# RHD2132_headstage1.net
KiCad netlist of a schematic drawn in EAGLE
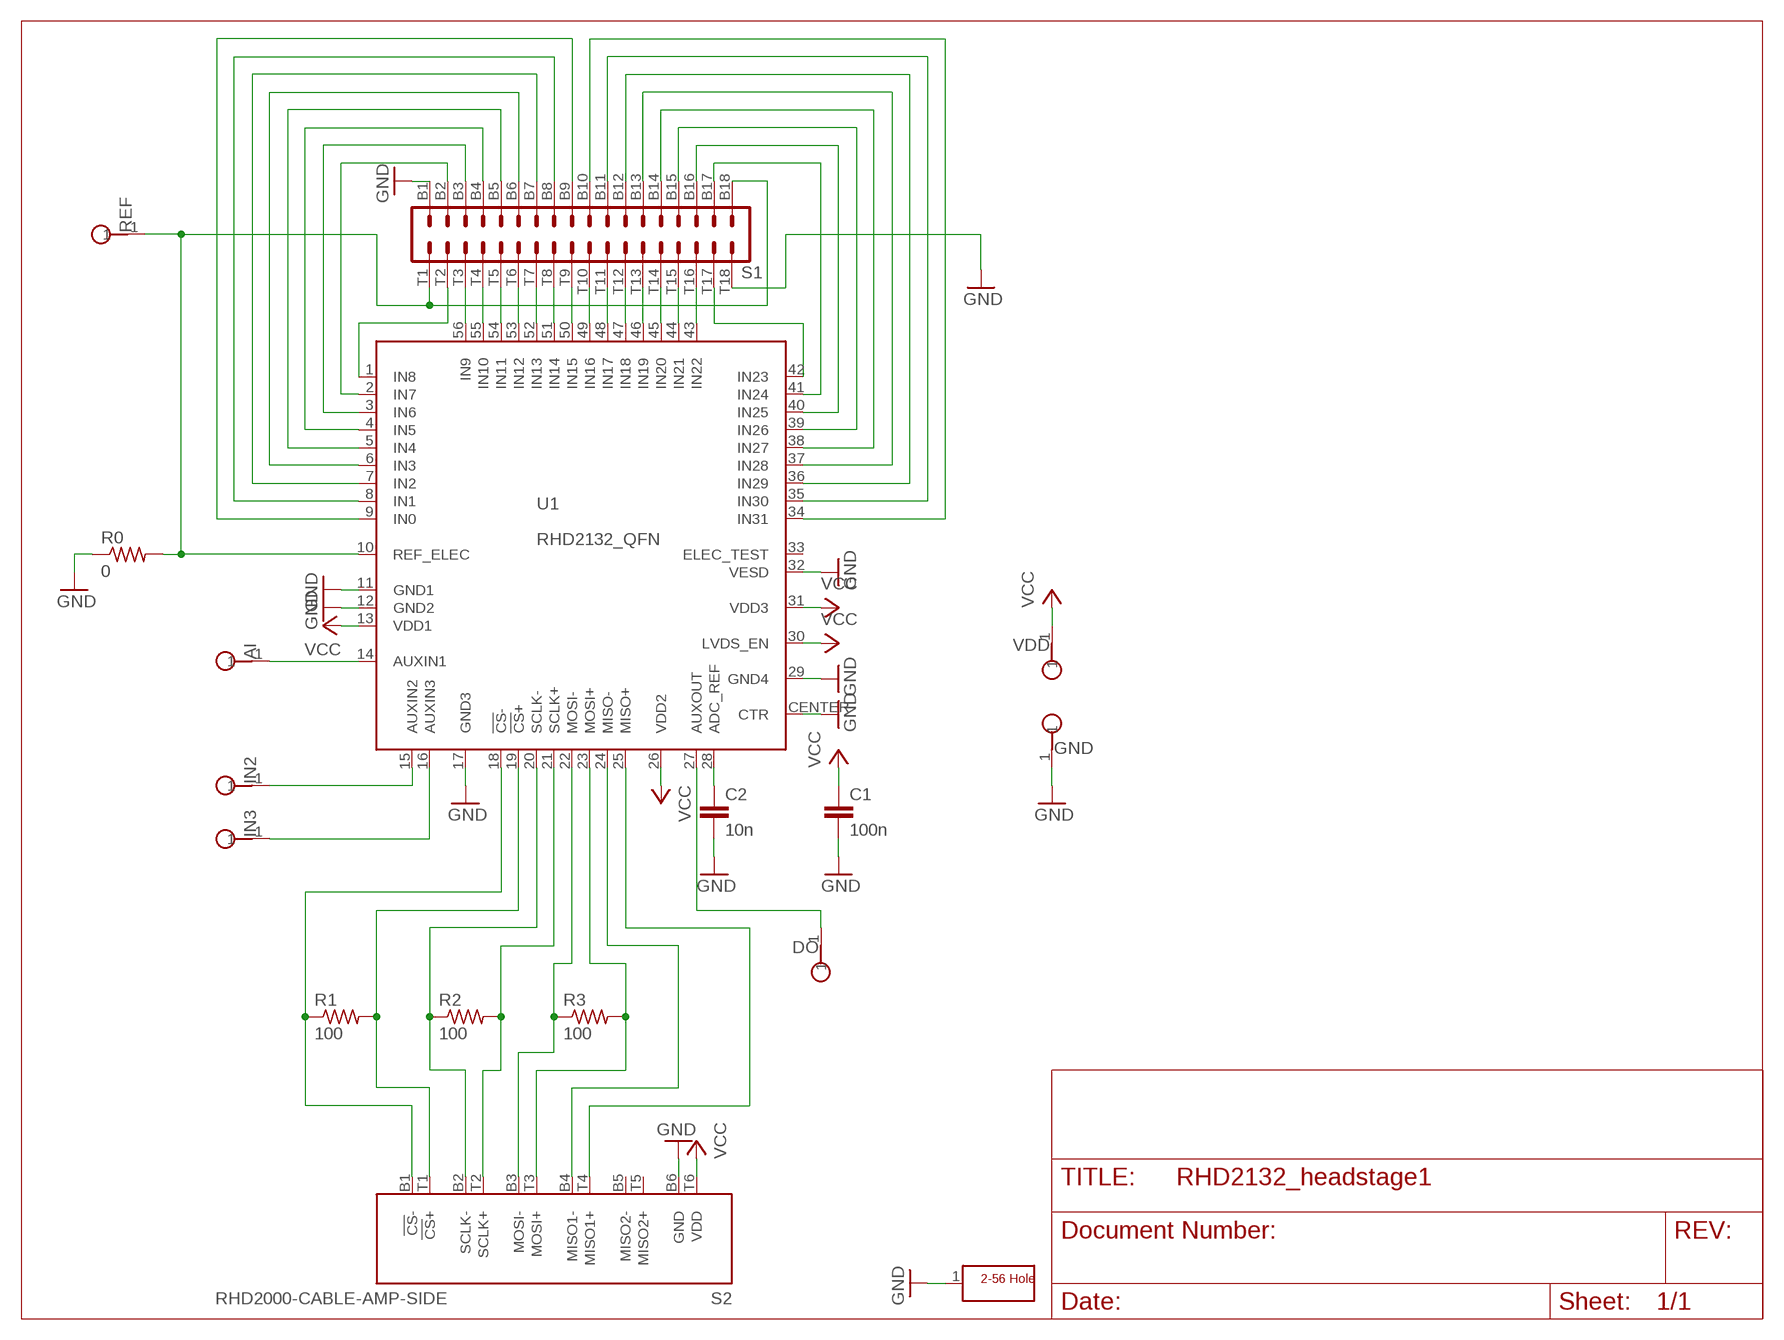
[diagram p0: schematic, sheet 1]

(export (version "E")
  (design (tool "Eeschema 10.0.6"))
  (components
    (comp (ref "AI")
      (value "TESTPOINT_SMALL")
      (footprint "eagle-import:TESTPOINT_SMALL")
      (libsource (lib "eagle-import") (part "TESTPOINT_SMALL"))
    )
    (comp (ref "C1")
      (value "100n")
      (footprint "eagle-import:0402")
      (libsource (lib "eagle-import") (part "C_0402"))
    )
    (comp (ref "C2")
      (value "10n")
      (footprint "eagle-import:0402")
      (libsource (lib "eagle-import") (part "C_0402"))
    )
    (comp (ref "DO")
      (value "TESTPOINT_SMALL")
      (footprint "eagle-import:TESTPOINT_SMALL")
      (libsource (lib "eagle-import") (part "TESTPOINT_SMALL"))
    )
    (comp (ref "GND")
      (value "TESTPOINT_SMALL")
      (footprint "eagle-import:TESTPOINT_SMALL")
      (libsource (lib "eagle-import") (part "TESTPOINT_SMALL"))
    )
    (comp (ref "H1")
      (value "SCREW_HOLE_2-56")
      (footprint "eagle-import:SCREW_HOLE_2-56")
      (libsource (lib "eagle-import") (part "SCREW_HOLE_2-56"))
    )
    (comp (ref "IN2")
      (value "TESTPOINT_SMALL")
      (footprint "eagle-import:TESTPOINT_SMALL")
      (libsource (lib "eagle-import") (part "TESTPOINT_SMALL"))
    )
    (comp (ref "IN3")
      (value "TESTPOINT_SMALL")
      (footprint "eagle-import:TESTPOINT_SMALL")
      (libsource (lib "eagle-import") (part "TESTPOINT_SMALL"))
    )
    (comp (ref "R0")
      (value "0")
      (footprint "eagle-import:0402")
      (libsource (lib "eagle-import") (part "R_0402"))
    )
    (comp (ref "R1")
      (value "100")
      (footprint "eagle-import:0402")
      (libsource (lib "eagle-import") (part "R_0402"))
    )
    (comp (ref "R2")
      (value "100")
      (footprint "eagle-import:0402")
      (libsource (lib "eagle-import") (part "R_0402"))
    )
    (comp (ref "R3")
      (value "100")
      (footprint "eagle-import:0402")
      (libsource (lib "eagle-import") (part "R_0402"))
    )
    (comp (ref "REF")
      (value "TESTPOINT_SMALL")
      (footprint "eagle-import:TESTPOINT_SMALL")
      (libsource (lib "eagle-import") (part "TESTPOINT_SMALL"))
    )
    (comp (ref "S1")
      (value "OMNETICS_A79025")
      (footprint "eagle-import:OMNETICS_A79025")
      (libsource (lib "eagle-import") (part "OMNETICS_A79025"))
    )
    (comp (ref "S2")
      (value "RHD2000-CABLE-AMP-SIDE")
      (footprint "eagle-import:OMNETICS_PZN-12-AA")
      (libsource (lib "eagle-import") (part "RHD2000-CABLE-AMP-SIDE"))
    )
    (comp (ref "U1")
      (value "RHD2132_QFN")
      (footprint "eagle-import:QFN56_8_X_8_LARGE")
      (libsource (lib "eagle-import") (part "RHD2132_QFN"))
    )
    (comp (ref "VDD")
      (value "TESTPOINT_SMALL")
      (footprint "eagle-import:TESTPOINT_SMALL")
      (libsource (lib "eagle-import") (part "TESTPOINT_SMALL"))
    )
  )
  (nets
    (net (code "1") (name "GND") (class "Default")
      (node (ref "C1") (pin "2") (pinfunction "2_2") (pintype "passive"))
      (node (ref "C2") (pin "2") (pinfunction "2_2") (pintype "passive"))
      (node (ref "GND") (pin "1") (pinfunction "1_1") (pintype "passive"))
      (node (ref "H1") (pin "1") (pinfunction "1_1") (pintype "passive"))
      (node (ref "R0") (pin "1") (pinfunction "1_1") (pintype "passive"))
      (node (ref "S1") (pin "B1") (pinfunction "B1_B1") (pintype "passive"))
      (node (ref "S1") (pin "T18") (pinfunction "T18_T18") (pintype "passive"))
      (node (ref "S2") (pin "B6") (pinfunction "GND_B6") (pintype "power_in"))
      (node (ref "U1") (pin "11") (pinfunction "GND1_11") (pintype "power_in"))
      (node (ref "U1") (pin "12") (pinfunction "GND2_12") (pintype "power_in"))
      (node (ref "U1") (pin "17") (pinfunction "GND3_17") (pintype "power_in"))
      (node (ref "U1") (pin "29") (pinfunction "GND4_29") (pintype "power_in"))
      (node (ref "U1") (pin "32") (pinfunction "VESD_32") (pintype "power_in"))
      (node (ref "U1") (pin "CENTER") (pinfunction "CTR_CENTER") (pintype "power_in"))
    )
    (net (code "2") (name "Net-(S2-MISO1+)") (class "Default")
      (node (ref "S2") (pin "T4") (pinfunction "MISO1+_T4") (pintype "bidirectional"))
      (node (ref "U1") (pin "25") (pinfunction "MISO+_25") (pintype "output"))
    )
    (net (code "3") (name "Net-(S2-MISO1-)") (class "Default")
      (node (ref "S2") (pin "B4") (pinfunction "MISO1-_B4") (pintype "bidirectional"))
      (node (ref "U1") (pin "24") (pinfunction "MISO-_24") (pintype "output"))
    )
    (net (code "4") (name "Net-(S2-MOSI+)") (class "Default")
      (node (ref "R3") (pin "2") (pinfunction "2_2") (pintype "passive"))
      (node (ref "S2") (pin "T3") (pinfunction "MOSI+_T3") (pintype "bidirectional"))
      (node (ref "U1") (pin "23") (pinfunction "MOSI+_23") (pintype "input"))
    )
    (net (code "5") (name "Net-(S2-MOSI-)") (class "Default")
      (node (ref "R3") (pin "1") (pinfunction "1_1") (pintype "passive"))
      (node (ref "S2") (pin "B3") (pinfunction "MOSI-_B3") (pintype "bidirectional"))
      (node (ref "U1") (pin "22") (pinfunction "MOSI-_22") (pintype "input"))
    )
    (net (code "6") (name "Net-(S2-SCLK+)") (class "Default")
      (node (ref "R2") (pin "2") (pinfunction "2_2") (pintype "passive"))
      (node (ref "S2") (pin "T2") (pinfunction "SCLK+_T2") (pintype "bidirectional"))
      (node (ref "U1") (pin "21") (pinfunction "SCLK+_21") (pintype "input"))
    )
    (net (code "7") (name "Net-(S2-SCLK-)") (class "Default")
      (node (ref "R2") (pin "1") (pinfunction "1_1") (pintype "passive"))
      (node (ref "S2") (pin "B2") (pinfunction "SCLK-_B2") (pintype "bidirectional"))
      (node (ref "U1") (pin "20") (pinfunction "SCLK-_20") (pintype "input"))
    )
    (net (code "8") (name "Net-(S2-~{CS}+)") (class "Default")
      (node (ref "R1") (pin "2") (pinfunction "2_2") (pintype "passive"))
      (node (ref "S2") (pin "T1") (pinfunction "~{CS}+_T1") (pintype "bidirectional"))
      (node (ref "U1") (pin "19") (pinfunction "~{CS}+_19") (pintype "input"))
    )
    (net (code "9") (name "Net-(S2-~{CS}-)") (class "Default")
      (node (ref "R1") (pin "1") (pinfunction "1_1") (pintype "passive"))
      (node (ref "S2") (pin "B1") (pinfunction "~{CS}-_B1") (pintype "bidirectional"))
      (node (ref "U1") (pin "18") (pinfunction "~{CS}-_18") (pintype "input"))
    )
    (net (code "10") (name "Net-(U1-ADC_REF)") (class "Default")
      (node (ref "C2") (pin "1") (pinfunction "1_1") (pintype "passive"))
      (node (ref "U1") (pin "28") (pinfunction "ADC_REF_28") (pintype "passive"))
    )
    (net (code "11") (name "Net-(U1-AUXIN1)") (class "Default")
      (node (ref "AI") (pin "1") (pinfunction "1_1") (pintype "passive"))
      (node (ref "U1") (pin "14") (pinfunction "AUXIN1_14") (pintype "input"))
    )
    (net (code "12") (name "Net-(U1-AUXIN2)") (class "Default")
      (node (ref "IN2") (pin "1") (pinfunction "1_1") (pintype "passive"))
      (node (ref "U1") (pin "15") (pinfunction "AUXIN2_15") (pintype "input"))
    )
    (net (code "13") (name "Net-(U1-AUXIN3)") (class "Default")
      (node (ref "IN3") (pin "1") (pinfunction "1_1") (pintype "passive"))
      (node (ref "U1") (pin "16") (pinfunction "AUXIN3_16") (pintype "input"))
    )
    (net (code "14") (name "Net-(U1-AUXOUT)") (class "Default")
      (node (ref "DO") (pin "1") (pinfunction "1_1") (pintype "passive"))
      (node (ref "U1") (pin "27") (pinfunction "AUXOUT_27") (pintype "tri_state"))
    )
    (net (code "15") (name "Net-(U1-IN0)") (class "Default")
      (node (ref "S1") (pin "B9") (pinfunction "B9_B9") (pintype "passive"))
      (node (ref "U1") (pin "9") (pinfunction "IN0_9") (pintype "input"))
    )
    (net (code "16") (name "Net-(U1-IN1)") (class "Default")
      (node (ref "S1") (pin "B8") (pinfunction "B8_B8") (pintype "passive"))
      (node (ref "U1") (pin "8") (pinfunction "IN1_8") (pintype "input"))
    )
    (net (code "17") (name "Net-(U1-IN2)") (class "Default")
      (node (ref "S1") (pin "B7") (pinfunction "B7_B7") (pintype "passive"))
      (node (ref "U1") (pin "7") (pinfunction "IN2_7") (pintype "input"))
    )
    (net (code "18") (name "Net-(U1-IN3)") (class "Default")
      (node (ref "S1") (pin "B6") (pinfunction "B6_B6") (pintype "passive"))
      (node (ref "U1") (pin "6") (pinfunction "IN3_6") (pintype "input"))
    )
    (net (code "19") (name "Net-(U1-IN4)") (class "Default")
      (node (ref "S1") (pin "B5") (pinfunction "B5_B5") (pintype "passive"))
      (node (ref "U1") (pin "5") (pinfunction "IN4_5") (pintype "input"))
    )
    (net (code "20") (name "Net-(U1-IN5)") (class "Default")
      (node (ref "S1") (pin "B4") (pinfunction "B4_B4") (pintype "passive"))
      (node (ref "U1") (pin "4") (pinfunction "IN5_4") (pintype "input"))
    )
    (net (code "21") (name "Net-(U1-IN6)") (class "Default")
      (node (ref "S1") (pin "B3") (pinfunction "B3_B3") (pintype "passive"))
      (node (ref "U1") (pin "3") (pinfunction "IN6_3") (pintype "input"))
    )
    (net (code "22") (name "Net-(U1-IN7)") (class "Default")
      (node (ref "S1") (pin "B2") (pinfunction "B2_B2") (pintype "passive"))
      (node (ref "U1") (pin "2") (pinfunction "IN7_2") (pintype "input"))
    )
    (net (code "23") (name "Net-(U1-IN8)") (class "Default")
      (node (ref "S1") (pin "T2") (pinfunction "T2_T2") (pintype "passive"))
      (node (ref "U1") (pin "1") (pinfunction "IN8_1") (pintype "input"))
    )
    (net (code "24") (name "Net-(U1-IN9)") (class "Default")
      (node (ref "S1") (pin "T3") (pinfunction "T3_T3") (pintype "passive"))
      (node (ref "U1") (pin "56") (pinfunction "IN9_56") (pintype "input"))
    )
    (net (code "25") (name "Net-(U1-IN10)") (class "Default")
      (node (ref "S1") (pin "T4") (pinfunction "T4_T4") (pintype "passive"))
      (node (ref "U1") (pin "55") (pinfunction "IN10_55") (pintype "input"))
    )
    (net (code "26") (name "Net-(U1-IN11)") (class "Default")
      (node (ref "S1") (pin "T5") (pinfunction "T5_T5") (pintype "passive"))
      (node (ref "U1") (pin "54") (pinfunction "IN11_54") (pintype "input"))
    )
    (net (code "27") (name "Net-(U1-IN12)") (class "Default")
      (node (ref "S1") (pin "T6") (pinfunction "T6_T6") (pintype "passive"))
      (node (ref "U1") (pin "53") (pinfunction "IN12_53") (pintype "input"))
    )
    (net (code "28") (name "Net-(U1-IN13)") (class "Default")
      (node (ref "S1") (pin "T7") (pinfunction "T7_T7") (pintype "passive"))
      (node (ref "U1") (pin "52") (pinfunction "IN13_52") (pintype "input"))
    )
    (net (code "29") (name "Net-(U1-IN14)") (class "Default")
      (node (ref "S1") (pin "T8") (pinfunction "T8_T8") (pintype "passive"))
      (node (ref "U1") (pin "51") (pinfunction "IN14_51") (pintype "input"))
    )
    (net (code "30") (name "Net-(U1-IN15)") (class "Default")
      (node (ref "S1") (pin "T9") (pinfunction "T9_T9") (pintype "passive"))
      (node (ref "U1") (pin "50") (pinfunction "IN15_50") (pintype "input"))
    )
    (net (code "31") (name "Net-(U1-IN16)") (class "Default")
      (node (ref "S1") (pin "T10") (pinfunction "T10_T10") (pintype "passive"))
      (node (ref "U1") (pin "49") (pinfunction "IN16_49") (pintype "input"))
    )
    (net (code "32") (name "Net-(U1-IN17)") (class "Default")
      (node (ref "S1") (pin "T11") (pinfunction "T11_T11") (pintype "passive"))
      (node (ref "U1") (pin "48") (pinfunction "IN17_48") (pintype "input"))
    )
    (net (code "33") (name "Net-(U1-IN18)") (class "Default")
      (node (ref "S1") (pin "T12") (pinfunction "T12_T12") (pintype "passive"))
      (node (ref "U1") (pin "47") (pinfunction "IN18_47") (pintype "input"))
    )
    (net (code "34") (name "Net-(U1-IN19)") (class "Default")
      (node (ref "S1") (pin "T13") (pinfunction "T13_T13") (pintype "passive"))
      (node (ref "U1") (pin "46") (pinfunction "IN19_46") (pintype "input"))
    )
    (net (code "35") (name "Net-(U1-IN20)") (class "Default")
      (node (ref "S1") (pin "T14") (pinfunction "T14_T14") (pintype "passive"))
      (node (ref "U1") (pin "45") (pinfunction "IN20_45") (pintype "input"))
    )
    (net (code "36") (name "Net-(U1-IN21)") (class "Default")
      (node (ref "S1") (pin "T15") (pinfunction "T15_T15") (pintype "passive"))
      (node (ref "U1") (pin "44") (pinfunction "IN21_44") (pintype "input"))
    )
    (net (code "37") (name "Net-(U1-IN22)") (class "Default")
      (node (ref "S1") (pin "T16") (pinfunction "T16_T16") (pintype "passive"))
      (node (ref "U1") (pin "43") (pinfunction "IN22_43") (pintype "input"))
    )
    (net (code "38") (name "Net-(U1-IN23)") (class "Default")
      (node (ref "S1") (pin "T17") (pinfunction "T17_T17") (pintype "passive"))
      (node (ref "U1") (pin "42") (pinfunction "IN23_42") (pintype "input"))
    )
    (net (code "39") (name "Net-(U1-IN24)") (class "Default")
      (node (ref "S1") (pin "B17") (pinfunction "B17_B17") (pintype "passive"))
      (node (ref "U1") (pin "41") (pinfunction "IN24_41") (pintype "input"))
    )
    (net (code "40") (name "Net-(U1-IN25)") (class "Default")
      (node (ref "S1") (pin "B16") (pinfunction "B16_B16") (pintype "passive"))
      (node (ref "U1") (pin "40") (pinfunction "IN25_40") (pintype "input"))
    )
    (net (code "41") (name "Net-(U1-IN26)") (class "Default")
      (node (ref "S1") (pin "B15") (pinfunction "B15_B15") (pintype "passive"))
      (node (ref "U1") (pin "39") (pinfunction "IN26_39") (pintype "input"))
    )
    (net (code "42") (name "Net-(U1-IN27)") (class "Default")
      (node (ref "S1") (pin "B14") (pinfunction "B14_B14") (pintype "passive"))
      (node (ref "U1") (pin "38") (pinfunction "IN27_38") (pintype "input"))
    )
    (net (code "43") (name "Net-(U1-IN28)") (class "Default")
      (node (ref "S1") (pin "B13") (pinfunction "B13_B13") (pintype "passive"))
      (node (ref "U1") (pin "37") (pinfunction "IN28_37") (pintype "input"))
    )
    (net (code "44") (name "Net-(U1-IN29)") (class "Default")
      (node (ref "S1") (pin "B12") (pinfunction "B12_B12") (pintype "passive"))
      (node (ref "U1") (pin "36") (pinfunction "IN29_36") (pintype "input"))
    )
    (net (code "45") (name "Net-(U1-IN30)") (class "Default")
      (node (ref "S1") (pin "B11") (pinfunction "B11_B11") (pintype "passive"))
      (node (ref "U1") (pin "35") (pinfunction "IN30_35") (pintype "input"))
    )
    (net (code "46") (name "Net-(U1-IN31)") (class "Default")
      (node (ref "S1") (pin "B10") (pinfunction "B10_B10") (pintype "passive"))
      (node (ref "U1") (pin "34") (pinfunction "IN31_34") (pintype "input"))
    )
    (net (code "47") (name "Net-(U1-REF_ELEC)") (class "Default")
      (node (ref "R0") (pin "2") (pinfunction "2_2") (pintype "passive"))
      (node (ref "REF") (pin "1") (pinfunction "1_1") (pintype "passive"))
      (node (ref "S1") (pin "B18") (pinfunction "B18_B18") (pintype "passive"))
      (node (ref "S1") (pin "T1") (pinfunction "T1_T1") (pintype "passive"))
      (node (ref "U1") (pin "10") (pinfunction "REF_ELEC_10") (pintype "input"))
    )
    (net (code "48") (name "VCC") (class "Default")
      (node (ref "C1") (pin "1") (pinfunction "1_1") (pintype "passive"))
      (node (ref "S2") (pin "T6") (pinfunction "VDD_T6") (pintype "bidirectional"))
      (node (ref "U1") (pin "13") (pinfunction "VDD1_13") (pintype "power_in"))
      (node (ref "U1") (pin "26") (pinfunction "VDD2_26") (pintype "power_in"))
      (node (ref "U1") (pin "30") (pinfunction "LVDS_EN_30") (pintype "input"))
      (node (ref "U1") (pin "31") (pinfunction "VDD3_31") (pintype "power_in"))
      (node (ref "VDD") (pin "1") (pinfunction "1_1") (pintype "passive"))
    )
    (net (code "49") (name "unconnected-(S2-MISO2+-PadT5)") (class "Default")
      (node (ref "S2") (pin "T5") (pinfunction "MISO2+_T5") (pintype "bidirectional"))
    )
    (net (code "50") (name "unconnected-(S2-MISO2--PadB5)") (class "Default")
      (node (ref "S2") (pin "B5") (pinfunction "MISO2-_B5") (pintype "bidirectional"))
    )
    (net (code "51") (name "unconnected-(U1-ELEC_TEST-Pad33)") (class "Default")
      (node (ref "U1") (pin "33") (pinfunction "ELEC_TEST_33") (pintype "input"))
    )
  )
)
